# optopair.net
KiCad netlist of a schematic drawn in EAGLE
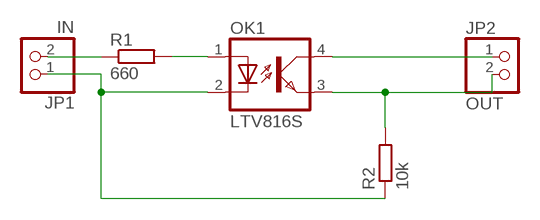
[diagram p0: schematic, sheet 1]

(export (version "E")
  (design (tool "Eeschema 10.0.6"))
  (components
    (comp (ref "JP1")
      (value "IN")
      (footprint "eagle-import:1X02")
      (libsource (lib "eagle-import") (part "PINHD-1X2"))
    )
    (comp (ref "JP2")
      (value "OUT")
      (footprint "eagle-import:1X02")
      (libsource (lib "eagle-import") (part "PINHD-1X2"))
    )
    (comp (ref "OK1")
      (value "LTV816S")
      (footprint "eagle-import:SMD4")
      (libsource (lib "eagle-import") (part "LTV816S"))
    )
    (comp (ref "R1")
      (value "660")
      (footprint "eagle-import:R0805")
      (libsource (lib "eagle-import") (part "R-EU_R0805"))
    )
    (comp (ref "R2")
      (value "10k")
      (footprint "eagle-import:R0805")
      (libsource (lib "eagle-import") (part "R-EU_R0805"))
    )
  )
  (nets
    (net (code "1") (name "Net-(JP1-Pad2)") (class "Default")
      (node (ref "JP1") (pin "2") (pinfunction "2_2") (pintype "passive"))
      (node (ref "R1") (pin "1") (pinfunction "1_1") (pintype "passive"))
    )
    (net (code "2") (name "Net-(OK1-A)") (class "Default")
      (node (ref "OK1") (pin "1") (pinfunction "A_1") (pintype "passive"))
      (node (ref "R1") (pin "2") (pinfunction "2_2") (pintype "passive"))
    )
    (net (code "3") (name "Net-(OK1-C)") (class "Default")
      (node (ref "JP1") (pin "1") (pinfunction "1_1") (pintype "passive"))
      (node (ref "OK1") (pin "2") (pinfunction "C_2") (pintype "passive"))
      (node (ref "R2") (pin "1") (pinfunction "1_1") (pintype "passive"))
    )
    (net (code "4") (name "Net-(OK1-COL)") (class "Default")
      (node (ref "JP2") (pin "1") (pinfunction "1_1") (pintype "passive"))
      (node (ref "OK1") (pin "4") (pinfunction "COL_4") (pintype "passive"))
    )
    (net (code "5") (name "Net-(OK1-EMIT)") (class "Default")
      (node (ref "JP2") (pin "2") (pinfunction "2_2") (pintype "passive"))
      (node (ref "OK1") (pin "3") (pinfunction "EMIT_3") (pintype "passive"))
      (node (ref "R2") (pin "2") (pinfunction "2_2") (pintype "passive"))
    )
  )
)
